# Sheet2.net
KiCad netlist of a schematic drawn in Altium Designer
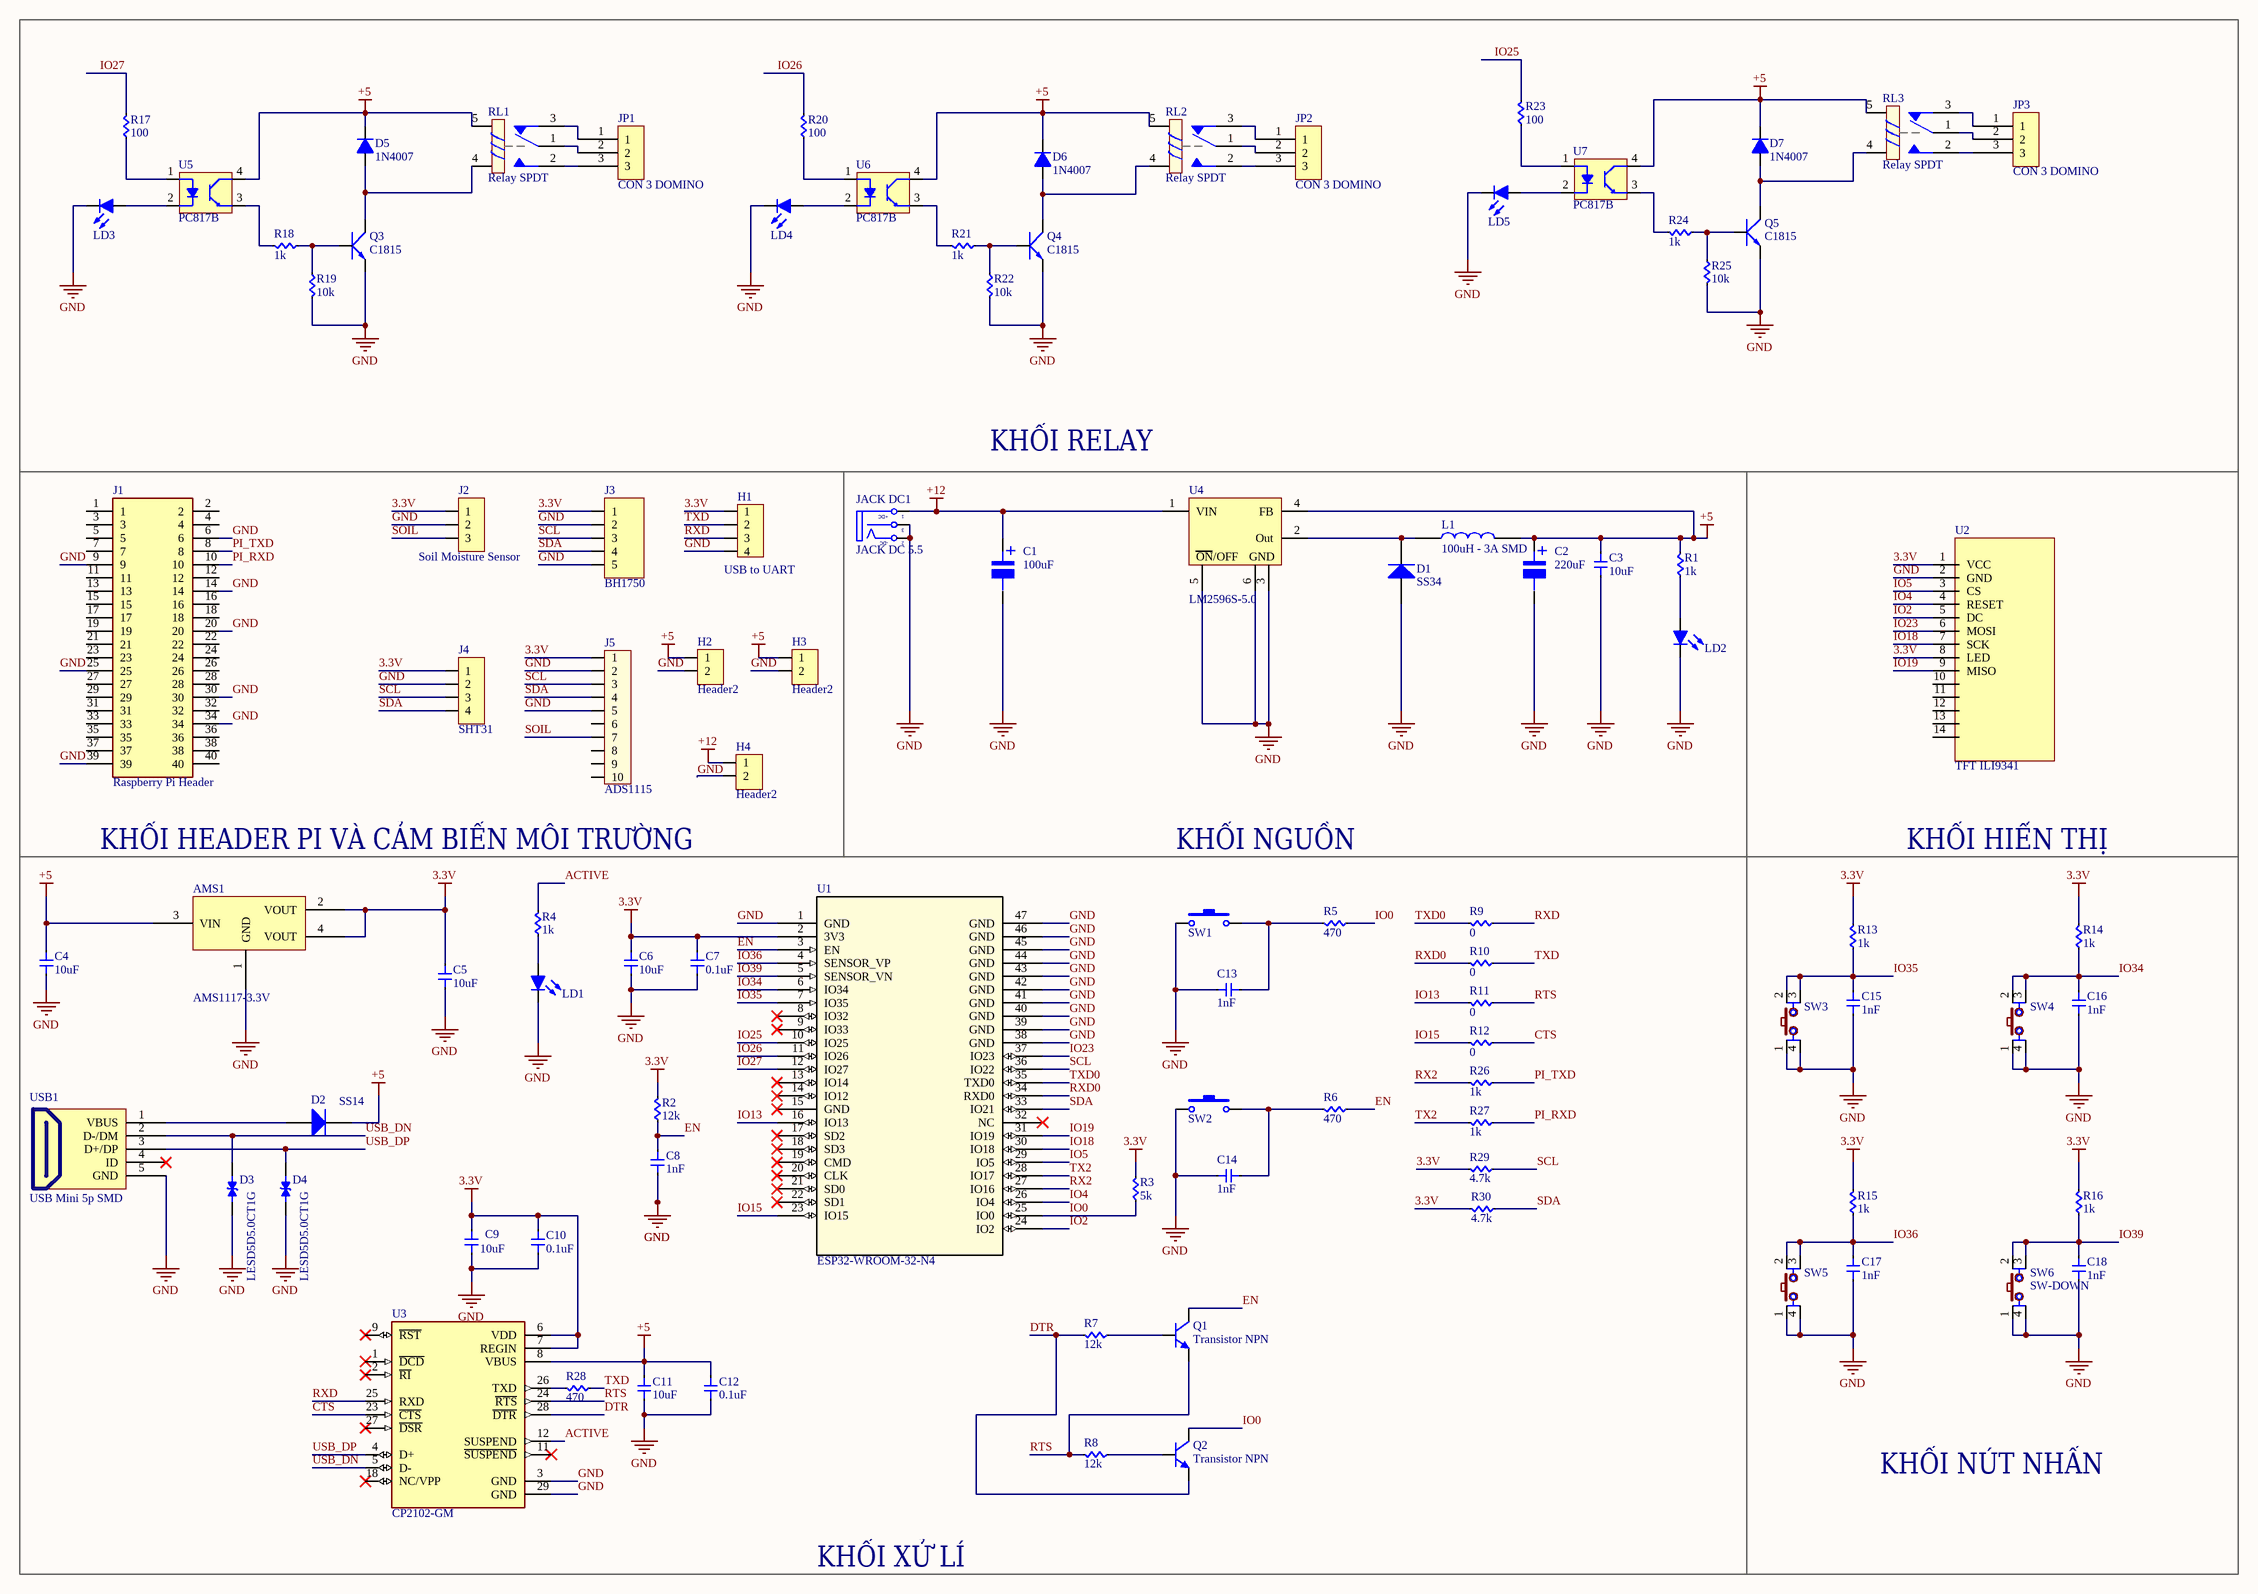
[diagram p0: Sheet2.SchDoc]

(export (version "E")
  (design (tool "Eeschema 10.0.6"))
  (components
    (comp (ref "AMS1")
      (value "AMS1117-3.3V")
      (footprint "SOT223")
      (description "Dán")
      (libsource (lib "IC") (part "AMS1117 SMD"))
    )
    (comp (ref "C1")
      (value "100uF")
      (footprint "tu nhom 6.3 (d)")
      (description "Dán")
      (libsource (lib "Capacitor") (part "Tu Nhom 100uF 16V"))
    )
    (comp (ref "C2")
      (value "220uF")
      (footprint "tu nhom 8 (e)")
      (description "Dán")
      (libsource (lib "Capacitor") (part "Tu Nhom 220uF 10V"))
    )
    (comp (ref "C3")
      (value "10uF")
      (footprint "Cap 0603")
      (description "Capacitor SMD 0603")
      (libsource (lib "General") (part "Cap 0603"))
    )
    (comp (ref "C4")
      (value "10uF")
      (footprint "Cap 0603")
      (description "Capacitor SMD 0603")
      (libsource (lib "General") (part "Cap 0603"))
    )
    (comp (ref "C5")
      (value "10uF")
      (footprint "Cap 0603")
      (description "Capacitor SMD 0603")
      (libsource (lib "General") (part "Cap 0603"))
    )
    (comp (ref "C6")
      (value "10uF")
      (footprint "Cap 0603")
      (description "Capacitor SMD 0603")
      (libsource (lib "General") (part "Cap 0603"))
    )
    (comp (ref "C7")
      (value "0.1uF")
      (footprint "Cap 0603")
      (description "Capacitor SMD 0603")
      (libsource (lib "General") (part "Cap 0603"))
    )
    (comp (ref "C8")
      (value "1nF")
      (footprint "Cap 0603")
      (description "Capacitor SMD 0603")
      (libsource (lib "General") (part "Cap 0603"))
    )
    (comp (ref "C9")
      (value "10uF")
      (footprint "Cap 0603")
      (description "Capacitor SMD 0603")
      (libsource (lib "General") (part "Cap 0603"))
    )
    (comp (ref "C10")
      (value "0.1uF")
      (footprint "Cap 0603")
      (description "Capacitor SMD 0603")
      (libsource (lib "General") (part "Cap 0603"))
    )
    (comp (ref "C11")
      (value "10uF")
      (footprint "Cap 0603")
      (description "Capacitor SMD 0603")
      (libsource (lib "General") (part "Cap 0603"))
    )
    (comp (ref "C12")
      (value "0.1uF")
      (footprint "Cap 0603")
      (description "Capacitor SMD 0603")
      (libsource (lib "General") (part "Cap 0603"))
    )
    (comp (ref "C13")
      (value "1nF")
      (footprint "Cap 0603")
      (description "Capacitor SMD 0603")
      (libsource (lib "General") (part "Cap 0603"))
    )
    (comp (ref "C14")
      (value "1nF")
      (footprint "Cap 0603")
      (description "Capacitor SMD 0603")
      (libsource (lib "General") (part "Cap 0603"))
    )
    (comp (ref "C15")
      (value "1nF")
      (footprint "Cap 0603")
      (description "Capacitor SMD 0603")
      (libsource (lib "General") (part "Cap 0603"))
    )
    (comp (ref "C16")
      (value "1nF")
      (footprint "Cap 0603")
      (description "Capacitor SMD 0603")
      (libsource (lib "General") (part "Cap 0603"))
    )
    (comp (ref "C17")
      (value "1nF")
      (footprint "Cap 0603")
      (description "Capacitor SMD 0603")
      (libsource (lib "General") (part "Cap 0603"))
    )
    (comp (ref "C18")
      (value "1nF")
      (footprint "Cap 0603")
      (description "Capacitor SMD 0603")
      (libsource (lib "General") (part "Cap 0603"))
    )
    (comp (ref "D1")
      (value "SS34")
      (footprint "DIODE SMA")
      (description "Dán")
      (libsource (lib "Diode") (part "Diode SS34 ( 1N5822 )"))
    )
    (comp (ref "D2")
      (value "SS14")
      (footprint "DIODE SMA")
      (description "Dán")
      (libsource (lib "Diode") (part "Diode SS14 ( 1N5819)"))
    )
    (comp (ref "D3")
      (value "LESD5D5.0CT1G")
      (footprint "TVS_LESD5D5.0CT1G")
      (description "Transient Voltage Suppressors for ESD Protection")
      (fields (field (name "MF") "Leshan Radio Co."))
      (libsource (lib "LESD5D5.0CT1G") (part "LESD5D5.0CT1G"))
    )
    (comp (ref "D4")
      (value "LESD5D5.0CT1G")
      (footprint "TVS_LESD5D5.0CT1G")
      (description "Transient Voltage Suppressors for ESD Protection")
      (fields (field (name "MF") "Leshan Radio Co."))
      (libsource (lib "LESD5D5.0CT1G") (part "LESD5D5.0CT1G"))
    )
    (comp (ref "D5")
      (value "1N4007")
      (footprint "DIODE 1A")
      (description "Cắm")
      (libsource (lib "Diode") (part "Diode 1N4007"))
    )
    (comp (ref "D6")
      (value "1N4007")
      (footprint "DIODE 1A")
      (description "Cắm")
      (libsource (lib "Diode") (part "Diode 1N4007"))
    )
    (comp (ref "D7")
      (value "1N4007")
      (footprint "DIODE 1A")
      (description "Cắm")
      (libsource (lib "Diode") (part "Diode 1N4007"))
    )
    (comp (ref "H1")
      (value "USB to UART")
      (footprint "HDR4")
      (description "Header IDC, 4 x 1 Pin Vertical 2.54mm Pitch (Non-Boxed, Male)")
      (fields
        (field (name "MANUFACTURER") "Würth Elektronik eiSos GmbH")
        (field (name "PARTNO") "613002143121")
        (field (name "CREATED BY") "Karrer Zheng")
      )
      (libsource (lib "Altium Library") (part "Header4"))
    )
    (comp (ref "H2")
      (value "Header2")
      (footprint "HDR2")
      (description "Header IDC, 2 x 1 Pin Vertical 2.54mm Pitch (Non-Boxed, Male)")
      (fields
        (field (name "MANUFACTURER") "Würth Elektronik eiSos GmbH")
        (field (name "PARTNO") "613002143121")
        (field (name "CREATED BY") "Karrer Zheng")
      )
      (libsource (lib "Altium Library") (part "Header2"))
    )
    (comp (ref "H3")
      (value "Header2")
      (footprint "HDR2")
      (description "Header IDC, 2 x 1 Pin Vertical 2.54mm Pitch (Non-Boxed, Male)")
      (fields
        (field (name "MANUFACTURER") "Würth Elektronik eiSos GmbH")
        (field (name "PARTNO") "613002143121")
        (field (name "CREATED BY") "Karrer Zheng")
      )
      (libsource (lib "Altium Library") (part "Header2"))
    )
    (comp (ref "H4")
      (value "Header2")
      (footprint "HDR2")
      (description "Header IDC, 2 x 1 Pin Vertical 2.54mm Pitch (Non-Boxed, Male)")
      (fields
        (field (name "MANUFACTURER") "Würth Elektronik eiSos GmbH")
        (field (name "PARTNO") "613002143121")
        (field (name "CREATED BY") "Karrer Zheng")
      )
      (libsource (lib "Altium Library") (part "Header2"))
    )
    (comp (ref "J1")
      (value "Raspberry Pi Header")
      (footprint "SAMESKY_SSK04-FPH-254-B20")
      (description "40 Position Header Connector 0.100 (2.54mm) Through Hole Gold")
      (fields (field (name "MF") "Same Sky (Formerly CUI Devices)") (field (name "MP") "SSK04-FPH-254-B20"))
      (libsource (lib "SSK04-FPH-254-B20") (part "SSK04-FPH-254-B20"))
    )
    (comp (ref "J2")
      (value "Soil Moisture Sensor")
      (footprint "JP3-C1T")
      (description "WR-PHD 2.54 mm Angled Socket Header")
      (fields
        (field (name "MANUFACTURER") "Würth Elektronik eiSos GmbH")
        (field (name "PARTNO") "613003143121")
        (field (name "CREATED BY") "Karrer Zheng")
      )
      (libsource (lib "Altium Library") (part "JP3"))
    )
    (comp (ref "J3")
      (value "BH1750")
      (footprint "JP5-C1T")
      (description "WR-PHD 2.54 mm Angled Socket Header")
      (fields
        (field (name "MANUFACTURER") "Würth Elektronik eiSos GmbH")
        (field (name "PARTNO") "613005143121")
        (field (name "CREATED BY") "Karrer Zheng")
      )
      (libsource (lib "Altium Library") (part "JP5"))
    )
    (comp (ref "J4")
      (value "SHT31")
      (footprint "JP4-C1T")
      (description "WR-PHD 2.54 mm Angled Socket Header")
      (fields
        (field (name "MANUFACTURER") "Würth Elektronik eiSos GmbH")
        (field (name "PARTNO") "613004143121")
        (field (name "CREATED BY") "Karrer Zheng")
      )
      (libsource (lib "Altium Library") (part "JP4"))
    )
    (comp (ref "J5")
      (value "ADS1115")
      (footprint "CON10")
      (description "Connector 10")
      (libsource (lib "Devzone_SCHLib") (part "Con10"))
    )
    (comp (ref "JACK DC1")
      (value "JACK DC 5.5")
      (footprint "JACK DC 5.5")
      (libsource (lib "Component") (part "JACK DC 5.5"))
    )
    (comp (ref "JP1")
      (value "CON 3 DOMINO")
      (footprint "CON 3")
      (libsource (lib "TIEN") (part "CON 3 DOMINO"))
    )
    (comp (ref "JP2")
      (value "CON 3 DOMINO")
      (footprint "CON 3")
      (libsource (lib "TIEN") (part "CON 3 DOMINO"))
    )
    (comp (ref "JP3")
      (value "CON 3 DOMINO")
      (footprint "CON 3")
      (libsource (lib "TIEN") (part "CON 3 DOMINO"))
    )
    (comp (ref "L1")
      (value "100uH - 3A SMD")
      (footprint "Cuon Cam 12x12x10")
      (description "Dán")
      (libsource (lib "Inductor") (part "CUON CAM 100uH SMD"))
    )
    (comp (ref "LD1")
      (value "Led")
      (footprint "Led 0805")
      (description "Typical LED")
      (libsource (lib "led") (part "Led"))
    )
    (comp (ref "LD2")
      (value "Led")
      (footprint "Led 0805")
      (description "Typical LED")
      (libsource (lib "led") (part "Led"))
    )
    (comp (ref "LD3")
      (value "Led")
      (footprint "Led 0805")
      (description "Typical LED")
      (libsource (lib "led") (part "Led"))
    )
    (comp (ref "LD4")
      (value "Led")
      (footprint "Led 0805")
      (description "Typical LED")
      (libsource (lib "led") (part "Led"))
    )
    (comp (ref "LD5")
      (value "Led")
      (footprint "Led 0805")
      (description "Typical LED")
      (libsource (lib "led") (part "Led"))
    )
    (comp (ref "Q1")
      (value "Transistor NPN")
      (footprint "SOT-23")
      (description "NPN Bipolar Transistor")
      (libsource (lib "chipfc_libs") (part "Transistor NPN"))
    )
    (comp (ref "Q2")
      (value "Transistor NPN")
      (footprint "SOT-23")
      (description "NPN Bipolar Transistor")
      (libsource (lib "chipfc_libs") (part "Transistor NPN"))
    )
    (comp (ref "Q3")
      (value "C1815")
      (footprint "TO92-123")
      (description "NPN 600mW, ECB")
      (libsource (lib "Altium Library") (part "2N222"))
    )
    (comp (ref "Q4")
      (value "C1815")
      (footprint "TO92-123")
      (description "NPN 600mW, ECB")
      (libsource (lib "Altium Library") (part "2N222"))
    )
    (comp (ref "Q5")
      (value "C1815")
      (footprint "TO92-123")
      (description "NPN 600mW, ECB")
      (libsource (lib "Altium Library") (part "2N222"))
    )
    (comp (ref "R1")
      (value "1k")
      (footprint "RES 0603")
      (description "RES SMD 0603")
      (fields
        (field (name "MANUFACTURER") "Vishay Dale")
        (field (name "MANUFACTURER PART NUMBER") "CRCW040210K0FKED")
      )
      (libsource (lib "General") (part "RES 0603"))
    )
    (comp (ref "R2")
      (value "12k")
      (footprint "RES 0603")
      (description "RES SMD 0603")
      (fields
        (field (name "MANUFACTURER") "Vishay Dale")
        (field (name "MANUFACTURER PART NUMBER") "CRCW040210K0FKED")
      )
      (libsource (lib "General") (part "RES 0603"))
    )
    (comp (ref "R3")
      (value "5k")
      (footprint "RES 0603")
      (description "RES SMD 0603")
      (fields
        (field (name "MANUFACTURER") "Vishay Dale")
        (field (name "MANUFACTURER PART NUMBER") "CRCW040210K0FKED")
      )
      (libsource (lib "General") (part "RES 0603"))
    )
    (comp (ref "R4")
      (value "1k")
      (footprint "RES 0603")
      (description "RES SMD 0603")
      (fields
        (field (name "MANUFACTURER") "Vishay Dale")
        (field (name "MANUFACTURER PART NUMBER") "CRCW040210K0FKED")
      )
      (libsource (lib "General") (part "RES 0603"))
    )
    (comp (ref "R5")
      (value "470")
      (footprint "RES 0603")
      (description "RES SMD 0603")
      (fields
        (field (name "MANUFACTURER") "Vishay Dale")
        (field (name "MANUFACTURER PART NUMBER") "CRCW040210K0FKED")
      )
      (libsource (lib "General") (part "RES 0603"))
    )
    (comp (ref "R6")
      (value "470")
      (footprint "RES 0603")
      (description "RES SMD 0603")
      (fields
        (field (name "MANUFACTURER") "Vishay Dale")
        (field (name "MANUFACTURER PART NUMBER") "CRCW040210K0FKED")
      )
      (libsource (lib "General") (part "RES 0603"))
    )
    (comp (ref "R7")
      (value "12k")
      (footprint "RES 0603")
      (description "RES SMD 0603")
      (fields
        (field (name "MANUFACTURER") "Vishay Dale")
        (field (name "MANUFACTURER PART NUMBER") "CRCW040210K0FKED")
      )
      (libsource (lib "General") (part "RES 0603"))
    )
    (comp (ref "R8")
      (value "12k")
      (footprint "RES 0603")
      (description "RES SMD 0603")
      (fields
        (field (name "MANUFACTURER") "Vishay Dale")
        (field (name "MANUFACTURER PART NUMBER") "CRCW040210K0FKED")
      )
      (libsource (lib "General") (part "RES 0603"))
    )
    (comp (ref "R9")
      (value "0")
      (footprint "RES 0603")
      (description "RES SMD 0603")
      (fields
        (field (name "MANUFACTURER") "Vishay Dale")
        (field (name "MANUFACTURER PART NUMBER") "CRCW040210K0FKED")
      )
      (libsource (lib "General") (part "RES 0603"))
    )
    (comp (ref "R10")
      (value "0")
      (footprint "RES 0603")
      (description "RES SMD 0603")
      (fields
        (field (name "MANUFACTURER") "Vishay Dale")
        (field (name "MANUFACTURER PART NUMBER") "CRCW040210K0FKED")
      )
      (libsource (lib "General") (part "RES 0603"))
    )
    (comp (ref "R11")
      (value "0")
      (footprint "RES 0603")
      (description "RES SMD 0603")
      (fields
        (field (name "MANUFACTURER") "Vishay Dale")
        (field (name "MANUFACTURER PART NUMBER") "CRCW040210K0FKED")
      )
      (libsource (lib "General") (part "RES 0603"))
    )
    (comp (ref "R12")
      (value "0")
      (footprint "RES 0603")
      (description "RES SMD 0603")
      (fields
        (field (name "MANUFACTURER") "Vishay Dale")
        (field (name "MANUFACTURER PART NUMBER") "CRCW040210K0FKED")
      )
      (libsource (lib "General") (part "RES 0603"))
    )
    (comp (ref "R13")
      (value "1k")
      (footprint "RES 0603")
      (description "RES SMD 0603")
      (fields
        (field (name "MANUFACTURER") "Vishay Dale")
        (field (name "MANUFACTURER PART NUMBER") "CRCW040210K0FKED")
      )
      (libsource (lib "General") (part "RES 0603"))
    )
    (comp (ref "R14")
      (value "1k")
      (footprint "RES 0603")
      (description "RES SMD 0603")
      (fields
        (field (name "MANUFACTURER") "Vishay Dale")
        (field (name "MANUFACTURER PART NUMBER") "CRCW040210K0FKED")
      )
      (libsource (lib "General") (part "RES 0603"))
    )
    (comp (ref "R15")
      (value "1k")
      (footprint "RES 0603")
      (description "RES SMD 0603")
      (fields
        (field (name "MANUFACTURER") "Vishay Dale")
        (field (name "MANUFACTURER PART NUMBER") "CRCW040210K0FKED")
      )
      (libsource (lib "General") (part "RES 0603"))
    )
    (comp (ref "R16")
      (value "1k")
      (footprint "RES 0603")
      (description "RES SMD 0603")
      (fields
        (field (name "MANUFACTURER") "Vishay Dale")
        (field (name "MANUFACTURER PART NUMBER") "CRCW040210K0FKED")
      )
      (libsource (lib "General") (part "RES 0603"))
    )
    (comp (ref "R17")
      (value "100")
      (footprint "RES 0603")
      (description "RES SMD 0603")
      (fields
        (field (name "MANUFACTURER") "Vishay Dale")
        (field (name "MANUFACTURER PART NUMBER") "CRCW040210K0FKED")
      )
      (libsource (lib "General") (part "RES 0603"))
    )
    (comp (ref "R18")
      (value "1k")
      (footprint "RES 0603")
      (description "RES SMD 0603")
      (fields
        (field (name "MANUFACTURER") "Vishay Dale")
        (field (name "MANUFACTURER PART NUMBER") "CRCW040210K0FKED")
      )
      (libsource (lib "General") (part "RES 0603"))
    )
    (comp (ref "R19")
      (value "10k")
      (footprint "RES 0603")
      (description "RES SMD 0603")
      (fields
        (field (name "MANUFACTURER") "Vishay Dale")
        (field (name "MANUFACTURER PART NUMBER") "CRCW040210K0FKED")
      )
      (libsource (lib "General") (part "RES 0603"))
    )
    (comp (ref "R20")
      (value "100")
      (footprint "RES 0603")
      (description "RES SMD 0603")
      (fields
        (field (name "MANUFACTURER") "Vishay Dale")
        (field (name "MANUFACTURER PART NUMBER") "CRCW040210K0FKED")
      )
      (libsource (lib "General") (part "RES 0603"))
    )
    (comp (ref "R21")
      (value "1k")
      (footprint "RES 0603")
      (description "RES SMD 0603")
      (fields
        (field (name "MANUFACTURER") "Vishay Dale")
        (field (name "MANUFACTURER PART NUMBER") "CRCW040210K0FKED")
      )
      (libsource (lib "General") (part "RES 0603"))
    )
    (comp (ref "R22")
      (value "10k")
      (footprint "RES 0603")
      (description "RES SMD 0603")
      (fields
        (field (name "MANUFACTURER") "Vishay Dale")
        (field (name "MANUFACTURER PART NUMBER") "CRCW040210K0FKED")
      )
      (libsource (lib "General") (part "RES 0603"))
    )
    (comp (ref "R23")
      (value "100")
      (footprint "RES 0603")
      (description "RES SMD 0603")
      (fields
        (field (name "MANUFACTURER") "Vishay Dale")
        (field (name "MANUFACTURER PART NUMBER") "CRCW040210K0FKED")
      )
      (libsource (lib "General") (part "RES 0603"))
    )
    (comp (ref "R24")
      (value "1k")
      (footprint "RES 0603")
      (description "RES SMD 0603")
      (fields
        (field (name "MANUFACTURER") "Vishay Dale")
        (field (name "MANUFACTURER PART NUMBER") "CRCW040210K0FKED")
      )
      (libsource (lib "General") (part "RES 0603"))
    )
    (comp (ref "R25")
      (value "10k")
      (footprint "RES 0603")
      (description "RES SMD 0603")
      (fields
        (field (name "MANUFACTURER") "Vishay Dale")
        (field (name "MANUFACTURER PART NUMBER") "CRCW040210K0FKED")
      )
      (libsource (lib "General") (part "RES 0603"))
    )
    (comp (ref "R26")
      (value "1k")
      (footprint "RES 0603")
      (description "RES SMD 0603")
      (fields
        (field (name "MANUFACTURER") "Vishay Dale")
        (field (name "MANUFACTURER PART NUMBER") "CRCW040210K0FKED")
      )
      (libsource (lib "General") (part "RES 0603"))
    )
    (comp (ref "R27")
      (value "1k")
      (footprint "RES 0603")
      (description "RES SMD 0603")
      (fields
        (field (name "MANUFACTURER") "Vishay Dale")
        (field (name "MANUFACTURER PART NUMBER") "CRCW040210K0FKED")
      )
      (libsource (lib "General") (part "RES 0603"))
    )
    (comp (ref "R28")
      (value "470")
      (footprint "RES 0603")
      (description "RES SMD 0603")
      (fields
        (field (name "MANUFACTURER") "Vishay Dale")
        (field (name "MANUFACTURER PART NUMBER") "CRCW040210K0FKED")
      )
      (libsource (lib "General") (part "RES 0603"))
    )
    (comp (ref "R29")
      (value "4.7k")
      (footprint "RES 0603")
      (description "RES SMD 0603")
      (fields
        (field (name "MANUFACTURER") "Vishay Dale")
        (field (name "MANUFACTURER PART NUMBER") "CRCW040210K0FKED")
      )
      (libsource (lib "General") (part "RES 0603"))
    )
    (comp (ref "R30")
      (value "4.7k")
      (footprint "RES 0603")
      (description "RES SMD 0603")
      (fields
        (field (name "MANUFACTURER") "Vishay Dale")
        (field (name "MANUFACTURER PART NUMBER") "CRCW040210K0FKED")
      )
      (libsource (lib "General") (part "RES 0603"))
    )
    (comp (ref "RL1")
      (value "Relay SPDT")
      (footprint "RL_SPDT_10A")
      (libsource (lib "chipfc_libs") (part "Relay SPDT"))
    )
    (comp (ref "RL2")
      (value "Relay SPDT")
      (footprint "RL_SPDT_10A")
      (libsource (lib "chipfc_libs") (part "Relay SPDT"))
    )
    (comp (ref "RL3")
      (value "Relay SPDT")
      (footprint "RL_SPDT_10A")
      (libsource (lib "chipfc_libs") (part "Relay SPDT"))
    )
    (comp (ref "SW1")
      (value "Nut Nhan 2 Chan SMD 3x6x2.5")
      (footprint "Nut Nhan 2 Chan SMD 3x6x2.5")
      (libsource (lib "Component") (part "Nut Nhan 2 Chan SMD 3x6x2.5"))
    )
    (comp (ref "SW2")
      (value "Nut Nhan 2 Chan SMD 3x6x2.5")
      (footprint "Nut Nhan 2 Chan SMD 3x6x2.5")
      (libsource (lib "Component") (part "Nut Nhan 2 Chan SMD 3x6x2.5"))
    )
    (comp (ref "SW3")
      (value "SW_CAPTURE")
      (footprint "SW2-DIP")
      (description "Switch button 4 pin")
      (libsource (lib "Altium Library") (part "SW4"))
    )
    (comp (ref "SW4")
      (value "SW_UP")
      (footprint "SW2-DIP")
      (description "Switch button 4 pin")
      (libsource (lib "Altium Library") (part "SW4"))
    )
    (comp (ref "SW5")
      (value "SW-OK")
      (footprint "SW2-DIP")
      (description "Switch button 4 pin")
      (libsource (lib "Altium Library") (part "SW4"))
    )
    (comp (ref "SW6")
      (value "SW-DOWN")
      (footprint "SW2-DIP")
      (description "Switch button 4 pin")
      (libsource (lib "Altium Library") (part "SW4"))
    )
    (comp (ref "U1")
      (value "ESP32-WROOM-32-N4")
      (footprint "MOD_ESP32-WROOM-32_EXP")
      (description "Description")
      (fields (field (name "COPYRIGHT") "Copyright (C) 2025 Ultra Librarian. All rights reserved."))
      (libsource (lib "ESP32-WROOM-32-N4") (part "ESP32-WROOM-32-N4"))
    )
    (comp (ref "U2")
      (value "TFT ILI9341")
      (footprint "TFT ILI9341")
      (libsource (lib "TIEN") (part "TFT ILI9341"))
    )
    (comp (ref "U3")
      (value "CP2102-GM")
      (footprint "QFN50P500X500X100-29N")
      (description "USB Bridge, USB to UART USB 2.0 UART Interface 28-QFN (5x5)")
      (fields (field (name "MF") "Silicon Labs"))
      (libsource (lib "CP2102-GM") (part "CP2102-GM"))
    )
    (comp (ref "U4")
      (value "LM2596S-5.0")
      (footprint "TO-263-5")
      (description "Simple Switcher 3A Step-Down Voltage Regulator")
      (libsource (lib "chipfc_libs") (part "LM2596S-5.0"))
    )
    (comp (ref "U5")
      (value "PC817B")
      (footprint "DIP 4")
      (libsource (lib "chipfc_libs") (part "Opto PC817B"))
    )
    (comp (ref "U6")
      (value "PC817B")
      (footprint "DIP 4")
      (libsource (lib "chipfc_libs") (part "Opto PC817B"))
    )
    (comp (ref "U7")
      (value "PC817B")
      (footprint "DIP 4")
      (libsource (lib "chipfc_libs") (part "Opto PC817B"))
    )
    (comp (ref "USB1")
      (value "USB Mini 5p SMD")
      (footprint "USB Mini 5p SMD")
      (description "USB Type B")
      (libsource (lib "Component") (part "USB Mini 5p SMD"))
    )
  )
  (nets
    (net (code "1") (name "+5") (class "Default")
      (node (ref "AMS1") (pin "3") (pinfunction "VIN_3") (pintype "passive"))
      (node (ref "C11") (pin "1") (pinfunction "1_1") (pintype "passive"))
      (node (ref "C12") (pin "1") (pinfunction "1_1") (pintype "passive"))
      (node (ref "C2") (pin "1") (pinfunction "1_1") (pintype "passive"))
      (node (ref "C3") (pin "1") (pinfunction "1_1") (pintype "passive"))
      (node (ref "C4") (pin "1") (pinfunction "1_1") (pintype "passive"))
      (node (ref "D2") (pin "2") (pinfunction "K_2") (pintype "passive"))
      (node (ref "D5") (pin "2") (pinfunction "K_2") (pintype "passive"))
      (node (ref "D6") (pin "2") (pinfunction "K_2") (pintype "passive"))
      (node (ref "D7") (pin "2") (pinfunction "K_2") (pintype "passive"))
      (node (ref "H2") (pin "1") (pinfunction "1_1") (pintype "passive"))
      (node (ref "H3") (pin "1") (pinfunction "1_1") (pintype "passive"))
      (node (ref "L1") (pin "2") (pinfunction "2_2") (pintype "passive"))
      (node (ref "R1") (pin "2") (pinfunction "2_2") (pintype "passive"))
      (node (ref "RL1") (pin "5") (pinfunction "COIL2_5") (pintype "passive"))
      (node (ref "RL2") (pin "5") (pinfunction "COIL2_5") (pintype "passive"))
      (node (ref "RL3") (pin "5") (pinfunction "COIL2_5") (pintype "passive"))
      (node (ref "U3") (pin "8") (pinfunction "VBUS_8") (pintype "power_in"))
      (node (ref "U4") (pin "4") (pinfunction "FB_4") (pintype "passive"))
      (node (ref "U5") (pin "4") (pinfunction "C_4") (pintype "passive"))
      (node (ref "U6") (pin "4") (pinfunction "C_4") (pintype "passive"))
      (node (ref "U7") (pin "4") (pinfunction "C_4") (pintype "passive"))
    )
    (net (code "2") (name "+12") (class "Default")
      (node (ref "C1") (pin "1") (pinfunction "1_1") (pintype "passive"))
      (node (ref "H4") (pin "1") (pinfunction "1_1") (pintype "passive"))
      (node (ref "JACK DC1") (pin "1") (pinfunction "T_1") (pintype "passive"))
      (node (ref "U4") (pin "1") (pinfunction "VIN_1") (pintype "passive"))
    )
    (net (code "3") (name "/ACTIVE") (class "Default")
      (node (ref "R4") (pin "2") (pinfunction "2_2") (pintype "passive"))
      (node (ref "U3") (pin "12") (pinfunction "SUSPEND_12") (pintype "output"))
    )
    (net (code "4") (name "/CTS") (class "Default")
      (node (ref "R12") (pin "1") (pinfunction "1_1") (pintype "passive"))
      (node (ref "U3") (pin "23") (pinfunction "~{CTS}_23") (pintype "input"))
    )
    (net (code "5") (name "/DTR") (class "Default")
      (node (ref "Q2") (pin "2") (pinfunction "E_2") (pintype "passive"))
      (node (ref "R7") (pin "2") (pinfunction "2_2") (pintype "passive"))
      (node (ref "U3") (pin "28") (pinfunction "~{DTR}_28") (pintype "output"))
    )
    (net (code "6") (name "/EN") (class "Default")
      (node (ref "C8") (pin "1") (pinfunction "1_1") (pintype "passive"))
      (node (ref "Q1") (pin "3") (pinfunction "C_3") (pintype "passive"))
      (node (ref "R2") (pin "1") (pinfunction "1_1") (pintype "passive"))
      (node (ref "R6") (pin "1") (pinfunction "1_1") (pintype "passive"))
      (node (ref "U1") (pin "3") (pinfunction "EN_3") (pintype "input"))
    )
    (net (code "7") (name "/IO0") (class "Default")
      (node (ref "Q2") (pin "3") (pinfunction "C_3") (pintype "passive"))
      (node (ref "R3") (pin "1") (pinfunction "1_1") (pintype "passive"))
      (node (ref "R5") (pin "1") (pinfunction "1_1") (pintype "passive"))
      (node (ref "U1") (pin "25") (pinfunction "IO0_25") (pintype "bidirectional"))
    )
    (net (code "8") (name "/IO2") (class "Default")
      (node (ref "U1") (pin "24") (pinfunction "IO2_24") (pintype "bidirectional"))
      (node (ref "U2") (pin "5") (pinfunction "DC_5") (pintype "passive"))
    )
    (net (code "9") (name "/IO4") (class "Default")
      (node (ref "U1") (pin "26") (pinfunction "IO4_26") (pintype "bidirectional"))
      (node (ref "U2") (pin "4") (pinfunction "RESET_4") (pintype "passive"))
    )
    (net (code "10") (name "/IO5") (class "Default")
      (node (ref "U1") (pin "29") (pinfunction "IO5_29") (pintype "bidirectional"))
      (node (ref "U2") (pin "3") (pinfunction "CS_3") (pintype "passive"))
    )
    (net (code "11") (name "/IO13") (class "Default")
      (node (ref "R11") (pin "2") (pinfunction "2_2") (pintype "passive"))
      (node (ref "U1") (pin "16") (pinfunction "IO13_16") (pintype "bidirectional"))
    )
    (net (code "12") (name "/IO15") (class "Default")
      (node (ref "R12") (pin "2") (pinfunction "2_2") (pintype "passive"))
      (node (ref "U1") (pin "23") (pinfunction "IO15_23") (pintype "bidirectional"))
    )
    (net (code "13") (name "/IO18") (class "Default")
      (node (ref "U1") (pin "30") (pinfunction "IO18_30") (pintype "bidirectional"))
      (node (ref "U2") (pin "7") (pinfunction "SCK_7") (pintype "passive"))
    )
    (net (code "14") (name "/IO19") (class "Default")
      (node (ref "U1") (pin "31") (pinfunction "IO19_31") (pintype "bidirectional"))
      (node (ref "U2") (pin "9") (pinfunction "MISO_9") (pintype "passive"))
    )
    (net (code "15") (name "/IO23") (class "Default")
      (node (ref "U1") (pin "37") (pinfunction "IO23_37") (pintype "bidirectional"))
      (node (ref "U2") (pin "6") (pinfunction "MOSI_6") (pintype "passive"))
    )
    (net (code "16") (name "/IO25") (class "Default")
      (node (ref "R23") (pin "2") (pinfunction "2_2") (pintype "passive"))
      (node (ref "U1") (pin "10") (pinfunction "IO25_10") (pintype "bidirectional"))
    )
    (net (code "17") (name "/IO26") (class "Default")
      (node (ref "R20") (pin "2") (pinfunction "2_2") (pintype "passive"))
      (node (ref "U1") (pin "11") (pinfunction "IO26_11") (pintype "bidirectional"))
    )
    (net (code "18") (name "/IO27") (class "Default")
      (node (ref "R17") (pin "2") (pinfunction "2_2") (pintype "passive"))
      (node (ref "U1") (pin "12") (pinfunction "IO27_12") (pintype "bidirectional"))
    )
    (net (code "19") (name "/IO34") (class "Default")
      (node (ref "C16") (pin "1") (pinfunction "1_1") (pintype "passive"))
      (node (ref "R14") (pin "1") (pinfunction "1_1") (pintype "passive"))
      (node (ref "SW4") (pin "2") (pinfunction "2_2") (pintype "passive"))
      (node (ref "SW4") (pin "3") (pinfunction "3_3") (pintype "passive"))
      (node (ref "U1") (pin "6") (pinfunction "IO34_6") (pintype "input"))
    )
    (net (code "20") (name "/IO35") (class "Default")
      (node (ref "C15") (pin "1") (pinfunction "1_1") (pintype "passive"))
      (node (ref "R13") (pin "1") (pinfunction "1_1") (pintype "passive"))
      (node (ref "SW3") (pin "2") (pinfunction "2_2") (pintype "passive"))
      (node (ref "SW3") (pin "3") (pinfunction "3_3") (pintype "passive"))
      (node (ref "U1") (pin "7") (pinfunction "IO35_7") (pintype "input"))
    )
    (net (code "21") (name "/IO36") (class "Default")
      (node (ref "C17") (pin "1") (pinfunction "1_1") (pintype "passive"))
      (node (ref "R15") (pin "1") (pinfunction "1_1") (pintype "passive"))
      (node (ref "SW5") (pin "2") (pinfunction "2_2") (pintype "passive"))
      (node (ref "SW5") (pin "3") (pinfunction "3_3") (pintype "passive"))
      (node (ref "U1") (pin "4") (pinfunction "SENSOR_VP_4") (pintype "input"))
    )
    (net (code "22") (name "/IO39") (class "Default")
      (node (ref "C18") (pin "1") (pinfunction "1_1") (pintype "passive"))
      (node (ref "R16") (pin "1") (pinfunction "1_1") (pintype "passive"))
      (node (ref "SW6") (pin "2") (pinfunction "2_2") (pintype "passive"))
      (node (ref "SW6") (pin "3") (pinfunction "3_3") (pintype "passive"))
      (node (ref "U1") (pin "5") (pinfunction "SENSOR_VN_5") (pintype "input"))
    )
    (net (code "23") (name "/PI_RXD") (class "Default")
      (node (ref "J1") (pin "10") (pinfunction "10_10") (pintype "passive"))
      (node (ref "R27") (pin "1") (pinfunction "1_1") (pintype "passive"))
    )
    (net (code "24") (name "/PI_TXD") (class "Default")
      (node (ref "J1") (pin "8") (pinfunction "8_8") (pintype "passive"))
      (node (ref "R26") (pin "1") (pinfunction "1_1") (pintype "passive"))
    )
    (net (code "25") (name "/RTS") (class "Default")
      (node (ref "Q1") (pin "2") (pinfunction "E_2") (pintype "passive"))
      (node (ref "R11") (pin "1") (pinfunction "1_1") (pintype "passive"))
      (node (ref "R8") (pin "2") (pinfunction "2_2") (pintype "passive"))
      (node (ref "U3") (pin "24") (pinfunction "~{RTS}_24") (pintype "output"))
    )
    (net (code "26") (name "/RX2") (class "Default")
      (node (ref "R26") (pin "2") (pinfunction "2_2") (pintype "passive"))
      (node (ref "U1") (pin "27") (pinfunction "IO16_27") (pintype "bidirectional"))
    )
    (net (code "27") (name "/RXD") (class "Default")
      (node (ref "H1") (pin "3") (pinfunction "3_3") (pintype "passive"))
      (node (ref "R9") (pin "1") (pinfunction "1_1") (pintype "passive"))
      (node (ref "U3") (pin "25") (pinfunction "RXD_25") (pintype "input"))
    )
    (net (code "28") (name "/RXD0") (class "Default")
      (node (ref "R10") (pin "2") (pinfunction "2_2") (pintype "passive"))
      (node (ref "U1") (pin "34") (pinfunction "RXD0_34") (pintype "bidirectional"))
    )
    (net (code "29") (name "/SCL") (class "Default")
      (node (ref "J3") (pin "3") (pinfunction "3_3") (pintype "passive"))
      (node (ref "J4") (pin "3") (pinfunction "3_3") (pintype "passive"))
      (node (ref "J5") (pin "3") (pinfunction "3_3") (pintype "passive"))
      (node (ref "R29") (pin "1") (pinfunction "1_1") (pintype "passive"))
      (node (ref "U1") (pin "36") (pinfunction "IO22_36") (pintype "bidirectional"))
    )
    (net (code "30") (name "/SDA") (class "Default")
      (node (ref "J3") (pin "4") (pinfunction "4_4") (pintype "passive"))
      (node (ref "J4") (pin "4") (pinfunction "4_4") (pintype "passive"))
      (node (ref "J5") (pin "4") (pinfunction "4_4") (pintype "passive"))
      (node (ref "R30") (pin "1") (pinfunction "1_1") (pintype "passive"))
      (node (ref "U1") (pin "33") (pinfunction "IO21_33") (pintype "bidirectional"))
    )
    (net (code "31") (name "/SOIL") (class "Default")
      (node (ref "J2") (pin "3") (pinfunction "3_3") (pintype "passive"))
      (node (ref "J5") (pin "7") (pinfunction "7_7") (pintype "passive"))
    )
    (net (code "32") (name "/TX2") (class "Default")
      (node (ref "R27") (pin "2") (pinfunction "2_2") (pintype "passive"))
      (node (ref "U1") (pin "28") (pinfunction "IO17_28") (pintype "bidirectional"))
    )
    (net (code "33") (name "/TXD") (class "Default")
      (node (ref "H1") (pin "2") (pinfunction "2_2") (pintype "passive"))
      (node (ref "R10") (pin "1") (pinfunction "1_1") (pintype "passive"))
      (node (ref "R28") (pin "1") (pinfunction "1_1") (pintype "passive"))
    )
    (net (code "34") (name "/TXD0") (class "Default")
      (node (ref "R9") (pin "2") (pinfunction "2_2") (pintype "passive"))
      (node (ref "U1") (pin "35") (pinfunction "TXD0_35") (pintype "bidirectional"))
    )
    (net (code "35") (name "/USB_DN") (class "Default")
      (node (ref "D3") (pin "2") (pinfunction "2_2") (pintype "passive"))
      (node (ref "U3") (pin "5") (pinfunction "D-_5") (pintype "bidirectional"))
      (node (ref "USB1") (pin "2") (pinfunction "D-/DM_2") (pintype "passive"))
    )
    (net (code "36") (name "/USB_DP") (class "Default")
      (node (ref "D4") (pin "2") (pinfunction "2_2") (pintype "passive"))
      (node (ref "U3") (pin "4") (pinfunction "D+_4") (pintype "bidirectional"))
      (node (ref "USB1") (pin "3") (pinfunction "D+/DP_3") (pintype "passive"))
    )
    (net (code "37") (name "3.3V") (class "Default")
      (node (ref "AMS1") (pin "2") (pinfunction "VOUT_2") (pintype "passive"))
      (node (ref "AMS1") (pin "4") (pinfunction "VOUT_4") (pintype "passive"))
      (node (ref "C10") (pin "1") (pinfunction "1_1") (pintype "passive"))
      (node (ref "C5") (pin "1") (pinfunction "1_1") (pintype "passive"))
      (node (ref "C6") (pin "1") (pinfunction "1_1") (pintype "passive"))
      (node (ref "C7") (pin "1") (pinfunction "1_1") (pintype "passive"))
      (node (ref "C9") (pin "1") (pinfunction "1_1") (pintype "passive"))
      (node (ref "H1") (pin "1") (pinfunction "1_1") (pintype "passive"))
      (node (ref "J2") (pin "1") (pinfunction "1_1") (pintype "passive"))
      (node (ref "J3") (pin "1") (pinfunction "1_1") (pintype "passive"))
      (node (ref "J4") (pin "1") (pinfunction "1_1") (pintype "passive"))
      (node (ref "J5") (pin "1") (pinfunction "1_1") (pintype "passive"))
      (node (ref "R13") (pin "2") (pinfunction "2_2") (pintype "passive"))
      (node (ref "R14") (pin "2") (pinfunction "2_2") (pintype "passive"))
      (node (ref "R15") (pin "2") (pinfunction "2_2") (pintype "passive"))
      (node (ref "R16") (pin "2") (pinfunction "2_2") (pintype "passive"))
      (node (ref "R2") (pin "2") (pinfunction "2_2") (pintype "passive"))
      (node (ref "R29") (pin "2") (pinfunction "2_2") (pintype "passive"))
      (node (ref "R3") (pin "2") (pinfunction "2_2") (pintype "passive"))
      (node (ref "R30") (pin "2") (pinfunction "2_2") (pintype "passive"))
      (node (ref "U1") (pin "2") (pinfunction "3V3_2") (pintype "power_in"))
      (node (ref "U2") (pin "1") (pinfunction "VCC_1") (pintype "passive"))
      (node (ref "U2") (pin "8") (pinfunction "LED_8") (pintype "passive"))
      (node (ref "U3") (pin "6") (pinfunction "VDD_6") (pintype "power_in"))
      (node (ref "U3") (pin "7") (pinfunction "REGIN_7") (pintype "power_in"))
    )
    (net (code "38") (name "GND") (class "Default")
      (node (ref "AMS1") (pin "1") (pinfunction "GND_1") (pintype "passive"))
      (node (ref "C1") (pin "2") (pinfunction "2_2") (pintype "passive"))
      (node (ref "C10") (pin "2") (pinfunction "2_2") (pintype "passive"))
      (node (ref "C11") (pin "2") (pinfunction "2_2") (pintype "passive"))
      (node (ref "C12") (pin "2") (pinfunction "2_2") (pintype "passive"))
      (node (ref "C13") (pin "1") (pinfunction "1_1") (pintype "passive"))
      (node (ref "C14") (pin "1") (pinfunction "1_1") (pintype "passive"))
      (node (ref "C15") (pin "2") (pinfunction "2_2") (pintype "passive"))
      (node (ref "C16") (pin "2") (pinfunction "2_2") (pintype "passive"))
      (node (ref "C17") (pin "2") (pinfunction "2_2") (pintype "passive"))
      (node (ref "C18") (pin "2") (pinfunction "2_2") (pintype "passive"))
      (node (ref "C2") (pin "2") (pinfunction "2_2") (pintype "passive"))
      (node (ref "C3") (pin "2") (pinfunction "2_2") (pintype "passive"))
      (node (ref "C4") (pin "2") (pinfunction "2_2") (pintype "passive"))
      (node (ref "C5") (pin "2") (pinfunction "2_2") (pintype "passive"))
      (node (ref "C6") (pin "2") (pinfunction "2_2") (pintype "passive"))
      (node (ref "C7") (pin "2") (pinfunction "2_2") (pintype "passive"))
      (node (ref "C8") (pin "2") (pinfunction "2_2") (pintype "passive"))
      (node (ref "C9") (pin "2") (pinfunction "2_2") (pintype "passive"))
      (node (ref "D1") (pin "1") (pinfunction "A_1") (pintype "passive"))
      (node (ref "D3") (pin "1") (pinfunction "1_1") (pintype "passive"))
      (node (ref "D4") (pin "1") (pinfunction "1_1") (pintype "passive"))
      (node (ref "H1") (pin "4") (pinfunction "4_4") (pintype "passive"))
      (node (ref "H2") (pin "2") (pinfunction "2_2") (pintype "passive"))
      (node (ref "H3") (pin "2") (pinfunction "2_2") (pintype "passive"))
      (node (ref "H4") (pin "2") (pinfunction "2_2") (pintype "passive"))
      (node (ref "J1") (pin "14") (pinfunction "14_14") (pintype "passive"))
      (node (ref "J1") (pin "20") (pinfunction "20_20") (pintype "passive"))
      (node (ref "J1") (pin "25") (pinfunction "25_25") (pintype "passive"))
      (node (ref "J1") (pin "30") (pinfunction "30_30") (pintype "passive"))
      (node (ref "J1") (pin "34") (pinfunction "34_34") (pintype "passive"))
      (node (ref "J1") (pin "39") (pinfunction "39_39") (pintype "passive"))
      (node (ref "J1") (pin "6") (pinfunction "6_6") (pintype "passive"))
      (node (ref "J1") (pin "9") (pinfunction "9_9") (pintype "passive"))
      (node (ref "J2") (pin "2") (pinfunction "2_2") (pintype "passive"))
      (node (ref "J3") (pin "2") (pinfunction "2_2") (pintype "passive"))
      (node (ref "J3") (pin "5") (pinfunction "5_5") (pintype "passive"))
      (node (ref "J4") (pin "2") (pinfunction "2_2") (pintype "passive"))
      (node (ref "J5") (pin "2") (pinfunction "2_2") (pintype "passive"))
      (node (ref "J5") (pin "5") (pinfunction "5_5") (pintype "passive"))
      (node (ref "JACK DC1") (pin "2") (pinfunction "TN_2") (pintype "passive"))
      (node (ref "JACK DC1") (pin "3") (pinfunction "S_3") (pintype "power_in"))
      (node (ref "LD1") (pin "2") (pinfunction "K_2") (pintype "passive"))
      (node (ref "LD2") (pin "2") (pinfunction "K_2") (pintype "passive"))
      (node (ref "LD3") (pin "2") (pinfunction "K_2") (pintype "passive"))
      (node (ref "LD4") (pin "2") (pinfunction "K_2") (pintype "passive"))
      (node (ref "LD5") (pin "2") (pinfunction "K_2") (pintype "passive"))
      (node (ref "Q3") (pin "1") (pinfunction "E_1") (pintype "passive"))
      (node (ref "Q4") (pin "1") (pinfunction "E_1") (pintype "passive"))
      (node (ref "Q5") (pin "1") (pinfunction "E_1") (pintype "passive"))
      (node (ref "R19") (pin "2") (pinfunction "2_2") (pintype "passive"))
      (node (ref "R22") (pin "2") (pinfunction "2_2") (pintype "passive"))
      (node (ref "R25") (pin "2") (pinfunction "2_2") (pintype "passive"))
      (node (ref "SW1") (pin "1") (pinfunction "1_1") (pintype "passive"))
      (node (ref "SW2") (pin "1") (pinfunction "1_1") (pintype "passive"))
      (node (ref "SW3") (pin "1") (pintype "passive"))
      (node (ref "SW3") (pin "4") (pinfunction "4_4") (pintype "passive"))
      (node (ref "SW4") (pin "1") (pintype "passive"))
      (node (ref "SW4") (pin "4") (pinfunction "4_4") (pintype "passive"))
      (node (ref "SW5") (pin "1") (pintype "passive"))
      (node (ref "SW5") (pin "4") (pinfunction "4_4") (pintype "passive"))
      (node (ref "SW6") (pin "1") (pintype "passive"))
      (node (ref "SW6") (pin "4") (pinfunction "4_4") (pintype "passive"))
      (node (ref "U1") (pin "1") (pinfunction "GND_1") (pintype "power_in"))
      (node (ref "U1") (pin "38") (pinfunction "GND_38") (pintype "power_in"))
      (node (ref "U1") (pin "39") (pinfunction "GND_39") (pintype "power_in"))
      (node (ref "U1") (pin "40") (pinfunction "GND_40") (pintype "power_in"))
      (node (ref "U1") (pin "41") (pinfunction "GND_41") (pintype "power_in"))
      (node (ref "U1") (pin "42") (pinfunction "GND_42") (pintype "power_in"))
      (node (ref "U1") (pin "43") (pinfunction "GND_43") (pintype "power_in"))
      (node (ref "U1") (pin "44") (pinfunction "GND_44") (pintype "power_in"))
      (node (ref "U1") (pin "45") (pinfunction "GND_45") (pintype "power_in"))
      (node (ref "U1") (pin "46") (pinfunction "GND_46") (pintype "power_in"))
      (node (ref "U1") (pin "47") (pinfunction "GND_47") (pintype "power_in"))
      (node (ref "U2") (pin "2") (pinfunction "GND_2") (pintype "passive"))
      (node (ref "U3") (pin "29") (pinfunction "GND_29") (pintype "power_in"))
      (node (ref "U3") (pin "3") (pinfunction "GND_3") (pintype "power_in"))
      (node (ref "U4") (pin "3") (pinfunction "GND_3") (pintype "passive"))
      (node (ref "U4") (pin "5") (pinfunction "~{ON}/OFF_5") (pintype "passive"))
      (node (ref "U4") (pin "6") (pinfunction "PAD_6") (pintype "passive"))
      (node (ref "USB1") (pin "5") (pinfunction "GND_5") (pintype "passive"))
    )
    (net (code "39") (name "Net-(C13-Pad2)") (class "Default")
      (node (ref "C13") (pin "2") (pinfunction "2_2") (pintype "passive"))
      (node (ref "R5") (pin "2") (pinfunction "2_2") (pintype "passive"))
      (node (ref "SW1") (pin "2") (pinfunction "2_2") (pintype "passive"))
    )
    (net (code "40") (name "Net-(C14-Pad2)") (class "Default")
      (node (ref "C14") (pin "2") (pinfunction "2_2") (pintype "passive"))
      (node (ref "R6") (pin "2") (pinfunction "2_2") (pintype "passive"))
      (node (ref "SW2") (pin "2") (pinfunction "2_2") (pintype "passive"))
    )
    (net (code "41") (name "Net-(D1-K)") (class "Default")
      (node (ref "D1") (pin "2") (pinfunction "K_2") (pintype "passive"))
      (node (ref "L1") (pin "1") (pinfunction "1_1") (pintype "passive"))
      (node (ref "U4") (pin "2") (pinfunction "Out_2") (pintype "passive"))
    )
    (net (code "42") (name "Net-(D2-A)") (class "Default")
      (node (ref "D2") (pin "1") (pinfunction "A_1") (pintype "passive"))
      (node (ref "USB1") (pin "1") (pinfunction "VBUS_1") (pintype "passive"))
    )
    (net (code "43") (name "Net-(D5-A)") (class "Default")
      (node (ref "D5") (pin "1") (pinfunction "A_1") (pintype "passive"))
      (node (ref "Q3") (pin "3") (pinfunction "C_3") (pintype "passive"))
      (node (ref "RL1") (pin "4") (pinfunction "COIL1_4") (pintype "passive"))
    )
    (net (code "44") (name "Net-(D6-A)") (class "Default")
      (node (ref "D6") (pin "1") (pinfunction "A_1") (pintype "passive"))
      (node (ref "Q4") (pin "3") (pinfunction "C_3") (pintype "passive"))
      (node (ref "RL2") (pin "4") (pinfunction "COIL1_4") (pintype "passive"))
    )
    (net (code "45") (name "Net-(D7-A)") (class "Default")
      (node (ref "D7") (pin "1") (pinfunction "A_1") (pintype "passive"))
      (node (ref "Q5") (pin "3") (pinfunction "C_3") (pintype "passive"))
      (node (ref "RL3") (pin "4") (pinfunction "COIL1_4") (pintype "passive"))
    )
    (net (code "46") (name "Net-(LD1-A)") (class "Default")
      (node (ref "LD1") (pin "1") (pinfunction "A_1") (pintype "passive"))
      (node (ref "R4") (pin "1") (pinfunction "1_1") (pintype "passive"))
    )
    (net (code "47") (name "Net-(LD2-A)") (class "Default")
      (node (ref "LD2") (pin "1") (pinfunction "A_1") (pintype "passive"))
      (node (ref "R1") (pin "1") (pinfunction "1_1") (pintype "passive"))
    )
    (net (code "48") (name "Net-(LD3-A)") (class "Default")
      (node (ref "LD3") (pin "1") (pinfunction "A_1") (pintype "passive"))
      (node (ref "U5") (pin "2") (pinfunction "K_2") (pintype "passive"))
    )
    (net (code "49") (name "Net-(LD4-A)") (class "Default")
      (node (ref "LD4") (pin "1") (pinfunction "A_1") (pintype "passive"))
      (node (ref "U6") (pin "2") (pinfunction "K_2") (pintype "passive"))
    )
    (net (code "50") (name "Net-(LD5-A)") (class "Default")
      (node (ref "LD5") (pin "1") (pinfunction "A_1") (pintype "passive"))
      (node (ref "U7") (pin "2") (pinfunction "K_2") (pintype "passive"))
    )
    (net (code "51") (name "Net-(Q1-B)") (class "Default")
      (node (ref "Q1") (pin "1") (pinfunction "B_1") (pintype "passive"))
      (node (ref "R7") (pin "1") (pinfunction "1_1") (pintype "passive"))
    )
    (net (code "52") (name "Net-(Q2-B)") (class "Default")
      (node (ref "Q2") (pin "1") (pinfunction "B_1") (pintype "passive"))
      (node (ref "R8") (pin "1") (pinfunction "1_1") (pintype "passive"))
    )
    (net (code "53") (name "Net-(Q3-B)") (class "Default")
      (node (ref "Q3") (pin "2") (pinfunction "B_2") (pintype "passive"))
      (node (ref "R18") (pin "1") (pinfunction "1_1") (pintype "passive"))
      (node (ref "R19") (pin "1") (pinfunction "1_1") (pintype "passive"))
    )
    (net (code "54") (name "Net-(Q4-B)") (class "Default")
      (node (ref "Q4") (pin "2") (pinfunction "B_2") (pintype "passive"))
      (node (ref "R21") (pin "1") (pinfunction "1_1") (pintype "passive"))
      (node (ref "R22") (pin "1") (pinfunction "1_1") (pintype "passive"))
    )
    (net (code "55") (name "Net-(Q5-B)") (class "Default")
      (node (ref "Q5") (pin "2") (pinfunction "B_2") (pintype "passive"))
      (node (ref "R24") (pin "1") (pinfunction "1_1") (pintype "passive"))
      (node (ref "R25") (pin "1") (pinfunction "1_1") (pintype "passive"))
    )
    (net (code "56") (name "Net-(RL1-COM)") (class "Default")
      (node (ref "JP1") (pin "2") (pinfunction "2_2") (pintype "passive"))
      (node (ref "RL1") (pin "1") (pinfunction "COM_1") (pintype "passive"))
    )
    (net (code "57") (name "Net-(RL1-NC)") (class "Default")
      (node (ref "JP1") (pin "1") (pinfunction "1_1") (pintype "passive"))
      (node (ref "RL1") (pin "3") (pinfunction "NC_3") (pintype "passive"))
    )
    (net (code "58") (name "Net-(RL1-NO)") (class "Default")
      (node (ref "JP1") (pin "3") (pinfunction "3_3") (pintype "passive"))
      (node (ref "RL1") (pin "2") (pinfunction "NO_2") (pintype "passive"))
    )
    (net (code "59") (name "Net-(RL2-COM)") (class "Default")
      (node (ref "JP2") (pin "2") (pinfunction "2_2") (pintype "passive"))
      (node (ref "RL2") (pin "1") (pinfunction "COM_1") (pintype "passive"))
    )
    (net (code "60") (name "Net-(RL2-NC)") (class "Default")
      (node (ref "JP2") (pin "1") (pinfunction "1_1") (pintype "passive"))
      (node (ref "RL2") (pin "3") (pinfunction "NC_3") (pintype "passive"))
    )
    (net (code "61") (name "Net-(RL2-NO)") (class "Default")
      (node (ref "JP2") (pin "3") (pinfunction "3_3") (pintype "passive"))
      (node (ref "RL2") (pin "2") (pinfunction "NO_2") (pintype "passive"))
    )
    (net (code "62") (name "Net-(RL3-COM)") (class "Default")
      (node (ref "JP3") (pin "2") (pinfunction "2_2") (pintype "passive"))
      (node (ref "RL3") (pin "1") (pinfunction "COM_1") (pintype "passive"))
    )
    (net (code "63") (name "Net-(RL3-NC)") (class "Default")
      (node (ref "JP3") (pin "1") (pinfunction "1_1") (pintype "passive"))
      (node (ref "RL3") (pin "3") (pinfunction "NC_3") (pintype "passive"))
    )
    (net (code "64") (name "Net-(RL3-NO)") (class "Default")
      (node (ref "JP3") (pin "3") (pinfunction "3_3") (pintype "passive"))
      (node (ref "RL3") (pin "2") (pinfunction "NO_2") (pintype "passive"))
    )
    (net (code "65") (name "Net-(U3-TXD)") (class "Default")
      (node (ref "R28") (pin "2") (pinfunction "2_2") (pintype "passive"))
      (node (ref "U3") (pin "26") (pinfunction "TXD_26") (pintype "output"))
    )
    (net (code "66") (name "Net-(U5-A)") (class "Default")
      (node (ref "R17") (pin "1") (pinfunction "1_1") (pintype "passive"))
      (node (ref "U5") (pin "1") (pinfunction "A_1") (pintype "passive"))
    )
    (net (code "67") (name "Net-(U5-E)") (class "Default")
      (node (ref "R18") (pin "2") (pinfunction "2_2") (pintype "passive"))
      (node (ref "U5") (pin "3") (pinfunction "E_3") (pintype "passive"))
    )
    (net (code "68") (name "Net-(U6-A)") (class "Default")
      (node (ref "R20") (pin "1") (pinfunction "1_1") (pintype "passive"))
      (node (ref "U6") (pin "1") (pinfunction "A_1") (pintype "passive"))
    )
    (net (code "69") (name "Net-(U6-E)") (class "Default")
      (node (ref "R21") (pin "2") (pinfunction "2_2") (pintype "passive"))
      (node (ref "U6") (pin "3") (pinfunction "E_3") (pintype "passive"))
    )
    (net (code "70") (name "Net-(U7-A)") (class "Default")
      (node (ref "R23") (pin "1") (pinfunction "1_1") (pintype "passive"))
      (node (ref "U7") (pin "1") (pinfunction "A_1") (pintype "passive"))
    )
    (net (code "71") (name "Net-(U7-E)") (class "Default")
      (node (ref "R24") (pin "2") (pinfunction "2_2") (pintype "passive"))
      (node (ref "U7") (pin "3") (pinfunction "E_3") (pintype "passive"))
    )
    (net (code "72") (name "unconnected-(J1-Pad1)") (class "Default")
      (node (ref "J1") (pin "1") (pinfunction "1_1") (pintype "passive"))
    )
    (net (code "73") (name "unconnected-(J1-Pad2)") (class "Default")
      (node (ref "J1") (pin "2") (pinfunction "2_2") (pintype "passive"))
    )
    (net (code "74") (name "unconnected-(J1-Pad3)") (class "Default")
      (node (ref "J1") (pin "3") (pinfunction "3_3") (pintype "passive"))
    )
    (net (code "75") (name "unconnected-(J1-Pad4)") (class "Default")
      (node (ref "J1") (pin "4") (pinfunction "4_4") (pintype "passive"))
    )
    (net (code "76") (name "unconnected-(J1-Pad5)") (class "Default")
      (node (ref "J1") (pin "5") (pinfunction "5_5") (pintype "passive"))
    )
    (net (code "77") (name "unconnected-(J1-Pad7)") (class "Default")
      (node (ref "J1") (pin "7") (pinfunction "7_7") (pintype "passive"))
    )
    (net (code "78") (name "unconnected-(J1-Pad11)") (class "Default")
      (node (ref "J1") (pin "11") (pinfunction "11_11") (pintype "passive"))
    )
    (net (code "79") (name "unconnected-(J1-Pad12)") (class "Default")
      (node (ref "J1") (pin "12") (pinfunction "12_12") (pintype "passive"))
    )
    (net (code "80") (name "unconnected-(J1-Pad13)") (class "Default")
      (node (ref "J1") (pin "13") (pinfunction "13_13") (pintype "passive"))
    )
    (net (code "81") (name "unconnected-(J1-Pad15)") (class "Default")
      (node (ref "J1") (pin "15") (pinfunction "15_15") (pintype "passive"))
    )
    (net (code "82") (name "unconnected-(J1-Pad16)") (class "Default")
      (node (ref "J1") (pin "16") (pinfunction "16_16") (pintype "passive"))
    )
    (net (code "83") (name "unconnected-(J1-Pad17)") (class "Default")
      (node (ref "J1") (pin "17") (pinfunction "17_17") (pintype "passive"))
    )
    (net (code "84") (name "unconnected-(J1-Pad18)") (class "Default")
      (node (ref "J1") (pin "18") (pinfunction "18_18") (pintype "passive"))
    )
    (net (code "85") (name "unconnected-(J1-Pad19)") (class "Default")
      (node (ref "J1") (pin "19") (pinfunction "19_19") (pintype "passive"))
    )
    (net (code "86") (name "unconnected-(J1-Pad21)") (class "Default")
      (node (ref "J1") (pin "21") (pinfunction "21_21") (pintype "passive"))
    )
    (net (code "87") (name "unconnected-(J1-Pad22)") (class "Default")
      (node (ref "J1") (pin "22") (pinfunction "22_22") (pintype "passive"))
    )
    (net (code "88") (name "unconnected-(J1-Pad23)") (class "Default")
      (node (ref "J1") (pin "23") (pinfunction "23_23") (pintype "passive"))
    )
    (net (code "89") (name "unconnected-(J1-Pad24)") (class "Default")
      (node (ref "J1") (pin "24") (pinfunction "24_24") (pintype "passive"))
    )
    (net (code "90") (name "unconnected-(J1-Pad26)") (class "Default")
      (node (ref "J1") (pin "26") (pinfunction "26_26") (pintype "passive"))
    )
    (net (code "91") (name "unconnected-(J1-Pad27)") (class "Default")
      (node (ref "J1") (pin "27") (pinfunction "27_27") (pintype "passive"))
    )
    (net (code "92") (name "unconnected-(J1-Pad28)") (class "Default")
      (node (ref "J1") (pin "28") (pinfunction "28_28") (pintype "passive"))
    )
    (net (code "93") (name "unconnected-(J1-Pad29)") (class "Default")
      (node (ref "J1") (pin "29") (pinfunction "29_29") (pintype "passive"))
    )
    (net (code "94") (name "unconnected-(J1-Pad31)") (class "Default")
      (node (ref "J1") (pin "31") (pinfunction "31_31") (pintype "passive"))
    )
    (net (code "95") (name "unconnected-(J1-Pad32)") (class "Default")
      (node (ref "J1") (pin "32") (pinfunction "32_32") (pintype "passive"))
    )
    (net (code "96") (name "unconnected-(J1-Pad33)") (class "Default")
      (node (ref "J1") (pin "33") (pinfunction "33_33") (pintype "passive"))
    )
    (net (code "97") (name "unconnected-(J1-Pad35)") (class "Default")
      (node (ref "J1") (pin "35") (pinfunction "35_35") (pintype "passive"))
    )
    (net (code "98") (name "unconnected-(J1-Pad36)") (class "Default")
      (node (ref "J1") (pin "36") (pinfunction "36_36") (pintype "passive"))
    )
    (net (code "99") (name "unconnected-(J1-Pad37)") (class "Default")
      (node (ref "J1") (pin "37") (pinfunction "37_37") (pintype "passive"))
    )
    (net (code "100") (name "unconnected-(J1-Pad38)") (class "Default")
      (node (ref "J1") (pin "38") (pinfunction "38_38") (pintype "passive"))
    )
    (net (code "101") (name "unconnected-(J1-Pad40)") (class "Default")
      (node (ref "J1") (pin "40") (pinfunction "40_40") (pintype "passive"))
    )
    (net (code "102") (name "unconnected-(J5-Pad6)") (class "Default")
      (node (ref "J5") (pin "6") (pinfunction "6_6") (pintype "passive"))
    )
    (net (code "103") (name "unconnected-(J5-Pad8)") (class "Default")
      (node (ref "J5") (pin "8") (pinfunction "8_8") (pintype "passive"))
    )
    (net (code "104") (name "unconnected-(J5-Pad9)") (class "Default")
      (node (ref "J5") (pin "9") (pinfunction "9_9") (pintype "passive"))
    )
    (net (code "105") (name "unconnected-(J5-Pad10)") (class "Default")
      (node (ref "J5") (pin "10") (pinfunction "10_10") (pintype "passive"))
    )
    (net (code "106") (name "unconnected-(U1-CLK-Pad20)") (class "Default")
      (node (ref "U1") (pin "20") (pinfunction "CLK_20") (pintype "bidirectional+no_connect"))
    )
    (net (code "107") (name "unconnected-(U1-CMD-Pad19)") (class "Default")
      (node (ref "U1") (pin "19") (pinfunction "CMD_19") (pintype "bidirectional+no_connect"))
    )
    (net (code "108") (name "unconnected-(U1-GND-Pad15)") (class "Default")
      (node (ref "U1") (pin "15") (pinfunction "GND_15") (pintype "power_in+no_connect"))
    )
    (net (code "109") (name "unconnected-(U1-IO12-Pad14)") (class "Default")
      (node (ref "U1") (pin "14") (pinfunction "IO12_14") (pintype "bidirectional+no_connect"))
    )
    (net (code "110") (name "unconnected-(U1-IO14-Pad13)") (class "Default")
      (node (ref "U1") (pin "13") (pinfunction "IO14_13") (pintype "bidirectional+no_connect"))
    )
    (net (code "111") (name "unconnected-(U1-IO32-Pad8)") (class "Default")
      (node (ref "U1") (pin "8") (pinfunction "IO32_8") (pintype "bidirectional+no_connect"))
    )
    (net (code "112") (name "unconnected-(U1-IO33-Pad9)") (class "Default")
      (node (ref "U1") (pin "9") (pinfunction "IO33_9") (pintype "bidirectional+no_connect"))
    )
    (net (code "113") (name "unconnected-(U1-NC-Pad32)") (class "Default")
      (node (ref "U1") (pin "32") (pinfunction "NC_32") (pintype "passive+no_connect"))
    )
    (net (code "114") (name "unconnected-(U1-SD0-Pad21)") (class "Default")
      (node (ref "U1") (pin "21") (pinfunction "SD0_21") (pintype "bidirectional+no_connect"))
    )
    (net (code "115") (name "unconnected-(U1-SD1-Pad22)") (class "Default")
      (node (ref "U1") (pin "22") (pinfunction "SD1_22") (pintype "bidirectional+no_connect"))
    )
    (net (code "116") (name "unconnected-(U1-SD2-Pad17)") (class "Default")
      (node (ref "U1") (pin "17") (pinfunction "SD2_17") (pintype "bidirectional+no_connect"))
    )
    (net (code "117") (name "unconnected-(U1-SD3-Pad18)") (class "Default")
      (node (ref "U1") (pin "18") (pinfunction "SD3_18") (pintype "bidirectional+no_connect"))
    )
    (net (code "118") (name "unconnected-(U2-DB11-Pad10)") (class "Default")
      (node (ref "U2") (pin "10") (pinfunction "DB11_10") (pintype "passive"))
    )
    (net (code "119") (name "unconnected-(U2-DB12-Pad11)") (class "Default")
      (node (ref "U2") (pin "11") (pinfunction "DB12_11") (pintype "passive"))
    )
    (net (code "120") (name "unconnected-(U2-DB13-Pad12)") (class "Default")
      (node (ref "U2") (pin "12") (pinfunction "DB13_12") (pintype "passive"))
    )
    (net (code "121") (name "unconnected-(U2-DB15-Pad14)") (class "Default")
      (node (ref "U2") (pin "14") (pinfunction "DB15_14") (pintype "passive"))
    )
    (net (code "122") (name "unconnected-(U2-DS14-Pad13)") (class "Default")
      (node (ref "U2") (pin "13") (pinfunction "DS14_13") (pintype "passive"))
    )
    (net (code "123") (name "unconnected-(U3-NC{slash}VPP-Pad18)") (class "Default")
      (node (ref "U3") (pin "18") (pinfunction "NC/VPP_18") (pintype "bidirectional+no_connect"))
    )
    (net (code "124") (name "unconnected-(U3-~{DCD}-Pad1)") (class "Default")
      (node (ref "U3") (pin "1") (pinfunction "~{DCD}_1") (pintype "input+no_connect"))
    )
    (net (code "125") (name "unconnected-(U3-~{DSR}-Pad27)") (class "Default")
      (node (ref "U3") (pin "27") (pinfunction "~{DSR}_27") (pintype "input+no_connect"))
    )
    (net (code "126") (name "unconnected-(U3-~{RI}-Pad2)") (class "Default")
      (node (ref "U3") (pin "2") (pinfunction "~{RI}_2") (pintype "input+no_connect"))
    )
    (net (code "127") (name "unconnected-(U3-~{RST}-Pad9)") (class "Default")
      (node (ref "U3") (pin "9") (pinfunction "~{RST}_9") (pintype "bidirectional+no_connect"))
    )
    (net (code "128") (name "unconnected-(U3-~{SUSPEND}-Pad11)") (class "Default")
      (node (ref "U3") (pin "11") (pinfunction "~{SUSPEND}_11") (pintype "output+no_connect"))
    )
    (net (code "129") (name "unconnected-(USB1-ID-Pad4)") (class "Default")
      (node (ref "USB1") (pin "4") (pinfunction "ID_4") (pintype "passive+no_connect"))
    )
  )
)
